# serial_led_controller.net
KiCad netlist of a schematic drawn in EAGLE
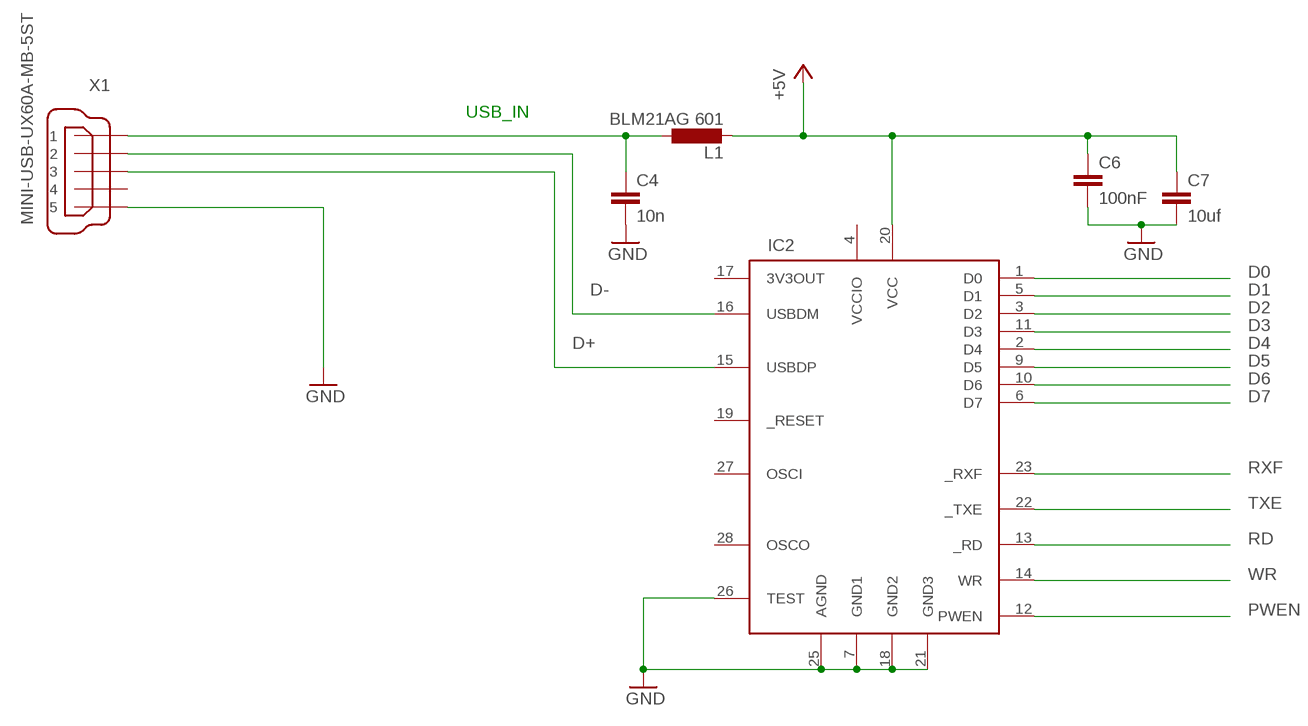
[diagram p0: schematic, sheet 1]
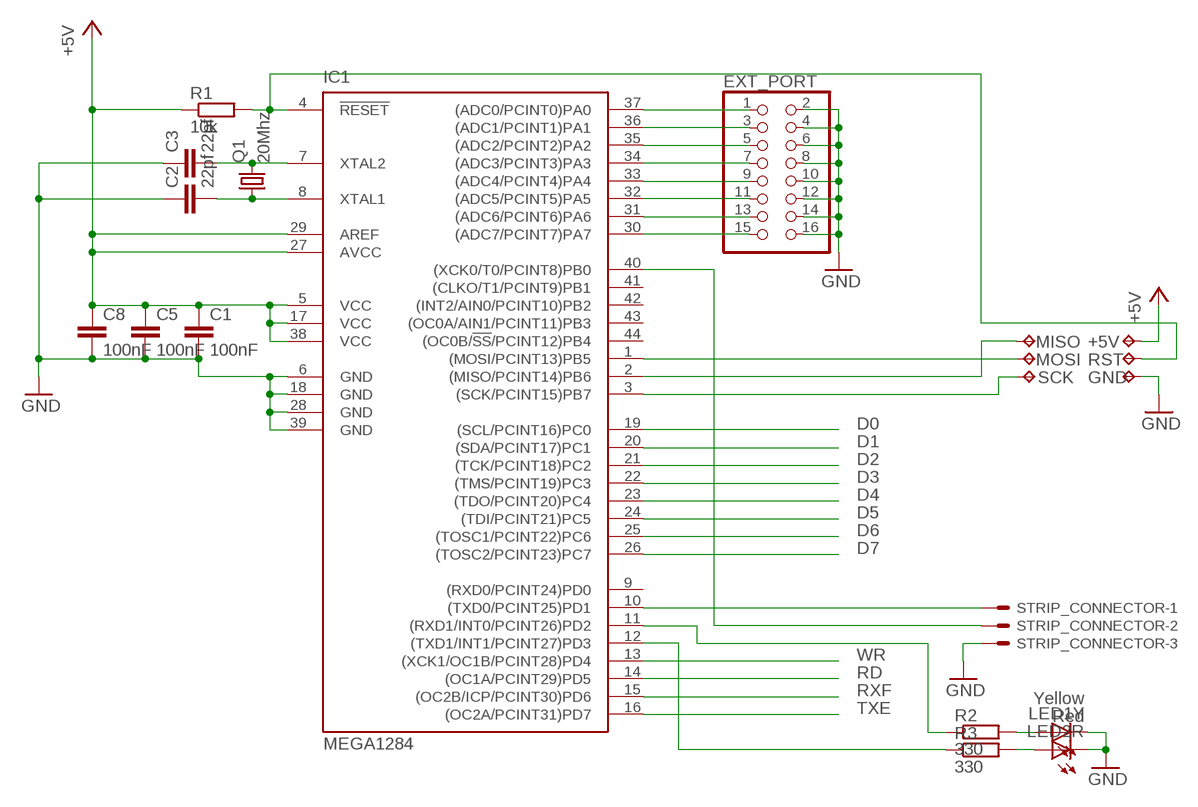
[diagram p1: schematic, sheet 2]

(export (version "E")
  (design (tool "Eeschema 10.0.6"))
  (components
    (comp (ref "+5V")
      (value "TPTP19R")
      (footprint "eagle-import:TP19R")
      (libsource (lib "eagle-import") (part "TPTP19R"))
    )
    (comp (ref "C1")
      (value "100nF")
      (footprint "eagle-import:C0603K")
      (libsource (lib "eagle-import") (part "C-EUC0603K"))
    )
    (comp (ref "C2")
      (value "22pf")
      (footprint "eagle-import:C0603K")
      (libsource (lib "eagle-import") (part "C-EUC0603K"))
    )
    (comp (ref "C3")
      (value "22pf")
      (footprint "eagle-import:C0603K")
      (libsource (lib "eagle-import") (part "C-EUC0603K"))
    )
    (comp (ref "C5")
      (value "100nF")
      (footprint "eagle-import:C0603K")
      (libsource (lib "eagle-import") (part "C-EUC0603K"))
    )
    (comp (ref "C8")
      (value "100nF")
      (footprint "eagle-import:C0603K")
      (libsource (lib "eagle-import") (part "C-EUC0603K"))
    )
    (comp (ref "EXT_PORT")
      (value "PINHD-2X8")
      (footprint "eagle-import:2X08")
      (libsource (lib "eagle-import") (part "PINHD-2X8"))
    )
    (comp (ref "GND")
      (value "TPTP19R")
      (footprint "eagle-import:TP19R")
      (libsource (lib "eagle-import") (part "TPTP19R"))
    )
    (comp (ref "IC1")
      (value "MEGA1284")
      (footprint "eagle-import:TQFP44")
      (libsource (lib "eagle-import") (part "MEGA164P/324P/644P-AU"))
    )
    (comp (ref "LED1Y")
      (value "Yellow")
      (footprint "eagle-import:CHIP-LED0603")
      (libsource (lib "eagle-import") (part "LEDCHIP-LED0603"))
    )
    (comp (ref "LED2R")
      (value "Red")
      (footprint "eagle-import:CHIP-LED0603")
      (libsource (lib "eagle-import") (part "LEDCHIP-LED0603"))
    )
    (comp (ref "MISO")
      (value "TPTP19R")
      (footprint "eagle-import:TP19R")
      (libsource (lib "eagle-import") (part "TPTP19R"))
    )
    (comp (ref "MOSI")
      (value "TPTP19R")
      (footprint "eagle-import:TP19R")
      (libsource (lib "eagle-import") (part "TPTP19R"))
    )
    (comp (ref "Q1")
      (value "20Mhz")
      (footprint "eagle-import:SM49")
      (libsource (lib "eagle-import") (part "CRYSTALSM49"))
    )
    (comp (ref "R1")
      (value "10k")
      (footprint "eagle-import:R0603")
      (libsource (lib "eagle-import") (part "R-EU_603"))
    )
    (comp (ref "R2")
      (value "330")
      (footprint "eagle-import:R0603")
      (libsource (lib "eagle-import") (part "R-EU_603"))
    )
    (comp (ref "R3")
      (value "330")
      (footprint "eagle-import:R0603")
      (libsource (lib "eagle-import") (part "R-EU_603"))
    )
    (comp (ref "RST")
      (value "TPTP19R")
      (footprint "eagle-import:TP19R")
      (libsource (lib "eagle-import") (part "TPTP19R"))
    )
    (comp (ref "SCK")
      (value "TPTP19R")
      (footprint "eagle-import:TP19R")
      (libsource (lib "eagle-import") (part "TPTP19R"))
    )
    (comp (ref "STRIP_CONNECTOR")
      (value "22-27-2031-03")
      (footprint "eagle-import:6410-03")
      (libsource (lib "eagle-import") (part "22-?-0327-2031"))
    )
    (comp (ref "C4")
      (value "10n")
      (footprint "eagle-import:C0603K")
      (libsource (lib "eagle-import") (part "C-EUC0603K"))
    )
    (comp (ref "C6")
      (value "100nF")
      (footprint "eagle-import:C0603K")
      (libsource (lib "eagle-import") (part "C-EUC0603K"))
    )
    (comp (ref "C7")
      (value "10uf")
      (footprint "eagle-import:C0603K")
      (libsource (lib "eagle-import") (part "C-EUC0603K"))
    )
    (comp (ref "IC2")
      (value "FT245RL")
      (footprint "eagle-import:SSOP28DB")
      (libsource (lib "eagle-import") (part "FT245RL"))
    )
    (comp (ref "L1")
      (value "BLM21AG 601")
      (footprint "eagle-import:L805")
      (libsource (lib "eagle-import") (part "L-EUL805"))
    )
    (comp (ref "X1")
      (value "MINI-USB-UX60A-MB-5ST")
      (footprint "eagle-import:UX60A-MB-5ST")
      (libsource (lib "eagle-import") (part "MINI-USB-UX60A-MB-5ST"))
    )
  )
  (nets
    (net (code "1") (name "+5V") (class "Default")
      (node (ref "+5V") (pin "TP") (pinfunction "TP_TP") (pintype "input"))
      (node (ref "C1") (pin "1") (pinfunction "1_1") (pintype "passive"))
      (node (ref "C5") (pin "1") (pinfunction "1_1") (pintype "passive"))
      (node (ref "C6") (pin "1") (pinfunction "1_1") (pintype "passive"))
      (node (ref "C7") (pin "1") (pinfunction "1_1") (pintype "passive"))
      (node (ref "C8") (pin "1") (pinfunction "1_1") (pintype "passive"))
      (node (ref "IC1") (pin "17") (pinfunction "VCC_17") (pintype "power_in"))
      (node (ref "IC1") (pin "27") (pinfunction "AVCC_27") (pintype "power_in"))
      (node (ref "IC1") (pin "29") (pinfunction "AREF_29") (pintype "power_in"))
      (node (ref "IC1") (pin "38") (pinfunction "VCC_38") (pintype "power_in"))
      (node (ref "IC1") (pin "5") (pinfunction "VCC_5") (pintype "power_in"))
      (node (ref "IC2") (pin "20") (pinfunction "VCC_20") (pintype "power_in"))
      (node (ref "L1") (pin "2") (pinfunction "2_2") (pintype "passive"))
      (node (ref "R1") (pin "1") (pinfunction "1_1") (pintype "passive"))
    )
    (net (code "2") (name "D+") (class "Default")
      (node (ref "IC2") (pin "15") (pinfunction "USBDP_15") (pintype "bidirectional"))
      (node (ref "X1") (pin "3") (pinfunction "3_3") (pintype "input"))
    )
    (net (code "3") (name "D-") (class "Default")
      (node (ref "IC2") (pin "16") (pinfunction "USBDM_16") (pintype "bidirectional"))
      (node (ref "X1") (pin "2") (pinfunction "2_2") (pintype "input"))
    )
    (net (code "4") (name "D0") (class "Default")
      (node (ref "IC1") (pin "19") (pinfunction "(SCL/PCINT16)PC0_19") (pintype "bidirectional"))
      (node (ref "IC2") (pin "1") (pinfunction "D0_1") (pintype "output"))
    )
    (net (code "5") (name "D1") (class "Default")
      (node (ref "IC1") (pin "20") (pinfunction "(SDA/PCINT17)PC1_20") (pintype "bidirectional"))
      (node (ref "IC2") (pin "5") (pinfunction "D1_5") (pintype "input"))
    )
    (net (code "6") (name "D2") (class "Default")
      (node (ref "IC1") (pin "21") (pinfunction "(TCK/PCINT18)PC2_21") (pintype "bidirectional"))
      (node (ref "IC2") (pin "3") (pinfunction "D2_3") (pintype "output"))
    )
    (net (code "7") (name "D3") (class "Default")
      (node (ref "IC1") (pin "22") (pinfunction "(TMS/PCINT19)PC3_22") (pintype "bidirectional"))
      (node (ref "IC2") (pin "11") (pinfunction "D3_11") (pintype "input"))
    )
    (net (code "8") (name "D4") (class "Default")
      (node (ref "IC1") (pin "23") (pinfunction "(TDO/PCINT20)PC4_23") (pintype "bidirectional"))
      (node (ref "IC2") (pin "2") (pinfunction "D4_2") (pintype "output"))
    )
    (net (code "9") (name "D5") (class "Default")
      (node (ref "IC1") (pin "24") (pinfunction "(TDI/PCINT21)PC5_24") (pintype "bidirectional"))
      (node (ref "IC2") (pin "9") (pinfunction "D5_9") (pintype "input"))
    )
    (net (code "10") (name "D6") (class "Default")
      (node (ref "IC1") (pin "25") (pinfunction "(TOSC1/PCINT22)PC6_25") (pintype "bidirectional"))
      (node (ref "IC2") (pin "10") (pinfunction "D6_10") (pintype "input"))
    )
    (net (code "11") (name "D7") (class "Default")
      (node (ref "IC1") (pin "26") (pinfunction "(TOSC2/PCINT23)PC7_26") (pintype "bidirectional"))
      (node (ref "IC2") (pin "6") (pinfunction "D7_6") (pintype "input"))
    )
    (net (code "12") (name "GND") (class "Default")
      (node (ref "C1") (pin "2") (pinfunction "2_2") (pintype "passive"))
      (node (ref "C2") (pin "1") (pinfunction "1_1") (pintype "passive"))
      (node (ref "C3") (pin "1") (pinfunction "1_1") (pintype "passive"))
      (node (ref "C4") (pin "2") (pinfunction "2_2") (pintype "passive"))
      (node (ref "C5") (pin "2") (pinfunction "2_2") (pintype "passive"))
      (node (ref "C6") (pin "2") (pinfunction "2_2") (pintype "passive"))
      (node (ref "C7") (pin "2") (pinfunction "2_2") (pintype "passive"))
      (node (ref "C8") (pin "2") (pinfunction "2_2") (pintype "passive"))
      (node (ref "EXT_PORT") (pin "10") (pinfunction "10_10") (pintype "passive"))
      (node (ref "EXT_PORT") (pin "12") (pinfunction "12_12") (pintype "passive"))
      (node (ref "EXT_PORT") (pin "14") (pinfunction "14_14") (pintype "passive"))
      (node (ref "EXT_PORT") (pin "16") (pinfunction "16_16") (pintype "passive"))
      (node (ref "EXT_PORT") (pin "2") (pinfunction "2_2") (pintype "passive"))
      (node (ref "EXT_PORT") (pin "4") (pinfunction "4_4") (pintype "passive"))
      (node (ref "EXT_PORT") (pin "6") (pinfunction "6_6") (pintype "passive"))
      (node (ref "EXT_PORT") (pin "8") (pinfunction "8_8") (pintype "passive"))
      (node (ref "GND") (pin "TP") (pinfunction "TP_TP") (pintype "input"))
      (node (ref "IC1") (pin "18") (pinfunction "GND_18") (pintype "power_in"))
      (node (ref "IC1") (pin "28") (pinfunction "GND_28") (pintype "power_in"))
      (node (ref "IC1") (pin "39") (pinfunction "GND_39") (pintype "power_in"))
      (node (ref "IC1") (pin "6") (pinfunction "GND_6") (pintype "power_in"))
      (node (ref "IC2") (pin "18") (pinfunction "GND2_18") (pintype "power_in"))
      (node (ref "IC2") (pin "21") (pinfunction "GND3_21") (pintype "power_in"))
      (node (ref "IC2") (pin "25") (pinfunction "AGND_25") (pintype "power_in"))
      (node (ref "IC2") (pin "26") (pinfunction "TEST_26") (pintype "input"))
      (node (ref "IC2") (pin "7") (pinfunction "GND1_7") (pintype "power_in"))
      (node (ref "LED1Y") (pin "C") (pinfunction "C_C") (pintype "passive"))
      (node (ref "LED2R") (pin "C") (pinfunction "C_C") (pintype "passive"))
      (node (ref "STRIP_CONNECTOR") (pin "3") (pinfunction "S_3") (pintype "passive"))
      (node (ref "X1") (pin "5") (pinfunction "5_5") (pintype "input"))
    )
    (net (code "13") (name "Net-(C4-Pad1)") (class "Default")
      (node (ref "C4") (pin "1") (pinfunction "1_1") (pintype "passive"))
      (node (ref "L1") (pin "1") (pinfunction "1_1") (pintype "passive"))
      (node (ref "X1") (pin "1") (pinfunction "1_1") (pintype "input"))
    )
    (net (code "14") (name "Net-(IC1-(ADC0{slash}PCINT0)PA0)") (class "Default")
      (node (ref "EXT_PORT") (pin "1") (pinfunction "1_1") (pintype "passive"))
      (node (ref "IC1") (pin "37") (pinfunction "(ADC0/PCINT0)PA0_37") (pintype "bidirectional"))
    )
    (net (code "15") (name "Net-(IC1-(ADC1{slash}PCINT1)PA1)") (class "Default")
      (node (ref "EXT_PORT") (pin "3") (pinfunction "3_3") (pintype "passive"))
      (node (ref "IC1") (pin "36") (pinfunction "(ADC1/PCINT1)PA1_36") (pintype "bidirectional"))
    )
    (net (code "16") (name "Net-(IC1-(ADC2{slash}PCINT2)PA2)") (class "Default")
      (node (ref "EXT_PORT") (pin "5") (pinfunction "5_5") (pintype "passive"))
      (node (ref "IC1") (pin "35") (pinfunction "(ADC2/PCINT2)PA2_35") (pintype "bidirectional"))
    )
    (net (code "17") (name "Net-(IC1-(ADC3{slash}PCINT3)PA3)") (class "Default")
      (node (ref "EXT_PORT") (pin "7") (pinfunction "7_7") (pintype "passive"))
      (node (ref "IC1") (pin "34") (pinfunction "(ADC3/PCINT3)PA3_34") (pintype "bidirectional"))
    )
    (net (code "18") (name "Net-(IC1-(ADC4{slash}PCINT4)PA4)") (class "Default")
      (node (ref "EXT_PORT") (pin "9") (pinfunction "9_9") (pintype "passive"))
      (node (ref "IC1") (pin "33") (pinfunction "(ADC4/PCINT4)PA4_33") (pintype "bidirectional"))
    )
    (net (code "19") (name "Net-(IC1-(ADC5{slash}PCINT5)PA5)") (class "Default")
      (node (ref "EXT_PORT") (pin "11") (pinfunction "11_11") (pintype "passive"))
      (node (ref "IC1") (pin "32") (pinfunction "(ADC5/PCINT5)PA5_32") (pintype "bidirectional"))
    )
    (net (code "20") (name "Net-(IC1-(ADC6{slash}PCINT6)PA6)") (class "Default")
      (node (ref "EXT_PORT") (pin "13") (pinfunction "13_13") (pintype "passive"))
      (node (ref "IC1") (pin "31") (pinfunction "(ADC6/PCINT6)PA6_31") (pintype "bidirectional"))
    )
    (net (code "21") (name "Net-(IC1-(ADC7{slash}PCINT7)PA7)") (class "Default")
      (node (ref "EXT_PORT") (pin "15") (pinfunction "15_15") (pintype "passive"))
      (node (ref "IC1") (pin "30") (pinfunction "(ADC7/PCINT7)PA7_30") (pintype "bidirectional"))
    )
    (net (code "22") (name "Net-(IC1-(MISO{slash}PCINT14)PB6)") (class "Default")
      (node (ref "IC1") (pin "2") (pinfunction "(MISO/PCINT14)PB6_2") (pintype "bidirectional"))
      (node (ref "MISO") (pin "TP") (pinfunction "TP_TP") (pintype "input"))
    )
    (net (code "23") (name "Net-(IC1-(MOSI{slash}PCINT13)PB5)") (class "Default")
      (node (ref "IC1") (pin "1") (pinfunction "(MOSI/PCINT13)PB5_1") (pintype "bidirectional"))
      (node (ref "MOSI") (pin "TP") (pinfunction "TP_TP") (pintype "input"))
    )
    (net (code "24") (name "Net-(IC1-(RXD1{slash}INT0{slash}PCINT26)PD2)") (class "Default")
      (node (ref "IC1") (pin "11") (pinfunction "(RXD1/INT0/PCINT26)PD2_11") (pintype "bidirectional"))
      (node (ref "R2") (pin "1") (pinfunction "1_1") (pintype "passive"))
    )
    (net (code "25") (name "Net-(IC1-(SCK{slash}PCINT15)PB7)") (class "Default")
      (node (ref "IC1") (pin "3") (pinfunction "(SCK/PCINT15)PB7_3") (pintype "bidirectional"))
      (node (ref "SCK") (pin "TP") (pinfunction "TP_TP") (pintype "input"))
    )
    (net (code "26") (name "Net-(IC1-(TXD0{slash}PCINT25)PD1)") (class "Default")
      (node (ref "IC1") (pin "10") (pinfunction "(TXD0/PCINT25)PD1_10") (pintype "bidirectional"))
      (node (ref "STRIP_CONNECTOR") (pin "1") (pinfunction "S_1") (pintype "passive"))
    )
    (net (code "27") (name "Net-(IC1-(TXD1{slash}INT1{slash}PCINT27)PD3)") (class "Default")
      (node (ref "IC1") (pin "12") (pinfunction "(TXD1/INT1/PCINT27)PD3_12") (pintype "bidirectional"))
      (node (ref "R3") (pin "1") (pinfunction "1_1") (pintype "passive"))
    )
    (net (code "28") (name "Net-(IC1-(XCK0{slash}T0{slash}PCINT8)PB0)") (class "Default")
      (node (ref "IC1") (pin "40") (pinfunction "(XCK0/T0/PCINT8)PB0_40") (pintype "bidirectional"))
      (node (ref "STRIP_CONNECTOR") (pin "2") (pinfunction "S_2") (pintype "passive"))
    )
    (net (code "29") (name "Net-(IC1-XTAL1)") (class "Default")
      (node (ref "C2") (pin "2") (pinfunction "2_2") (pintype "passive"))
      (node (ref "IC1") (pin "8") (pinfunction "XTAL1_8") (pintype "input"))
      (node (ref "Q1") (pin "1") (pinfunction "1_1") (pintype "passive"))
    )
    (net (code "30") (name "Net-(IC1-XTAL2)") (class "Default")
      (node (ref "C3") (pin "2") (pinfunction "2_2") (pintype "passive"))
      (node (ref "IC1") (pin "7") (pinfunction "XTAL2_7") (pintype "output"))
      (node (ref "Q1") (pin "2") (pinfunction "2_2") (pintype "passive"))
    )
    (net (code "31") (name "Net-(IC1-~{RESET})") (class "Default")
      (node (ref "IC1") (pin "4") (pinfunction "~{RESET}_4") (pintype "input"))
      (node (ref "R1") (pin "2") (pinfunction "2_2") (pintype "passive"))
      (node (ref "RST") (pin "TP") (pinfunction "TP_TP") (pintype "input"))
    )
    (net (code "32") (name "Net-(LED1Y-PadA)") (class "Default")
      (node (ref "LED1Y") (pin "A") (pinfunction "A_A") (pintype "passive"))
      (node (ref "R2") (pin "2") (pinfunction "2_2") (pintype "passive"))
    )
    (net (code "33") (name "Net-(LED2R-PadA)") (class "Default")
      (node (ref "LED2R") (pin "A") (pinfunction "A_A") (pintype "passive"))
      (node (ref "R3") (pin "2") (pinfunction "2_2") (pintype "passive"))
    )
    (net (code "34") (name "PWEN") (class "Default")
      (node (ref "IC2") (pin "12") (pinfunction "PWEN_12") (pintype "bidirectional"))
    )
    (net (code "35") (name "RD") (class "Default")
      (node (ref "IC1") (pin "14") (pinfunction "(OC1A/PCINT29)PD5_14") (pintype "bidirectional"))
      (node (ref "IC2") (pin "13") (pinfunction "_RD_13") (pintype "bidirectional"))
    )
    (net (code "36") (name "RXF") (class "Default")
      (node (ref "IC1") (pin "15") (pinfunction "(OC2B/ICP/PCINT30)PD6_15") (pintype "bidirectional"))
      (node (ref "IC2") (pin "23") (pinfunction "_RXF_23") (pintype "bidirectional"))
    )
    (net (code "37") (name "TXE") (class "Default")
      (node (ref "IC1") (pin "16") (pinfunction "(OC2A/PCINT31)PD7_16") (pintype "bidirectional"))
      (node (ref "IC2") (pin "22") (pinfunction "_TXE_22") (pintype "bidirectional"))
    )
    (net (code "38") (name "VCCIO") (class "Default")
      (node (ref "IC2") (pin "4") (pinfunction "VCCIO_4") (pintype "power_in"))
    )
    (net (code "39") (name "WR") (class "Default")
      (node (ref "IC1") (pin "13") (pinfunction "(XCK1/OC1B/PCINT28)PD4_13") (pintype "bidirectional"))
      (node (ref "IC2") (pin "14") (pinfunction "WR_14") (pintype "bidirectional"))
    )
    (net (code "40") (name "unconnected-(IC1-(CLKO{slash}T1{slash}PCINT9)PB1-Pad41)") (class "Default")
      (node (ref "IC1") (pin "41") (pinfunction "(CLKO/T1/PCINT9)PB1_41") (pintype "bidirectional"))
    )
    (net (code "41") (name "unconnected-(IC1-(INT2{slash}AIN0{slash}PCINT10)PB2-Pad42)") (class "Default")
      (node (ref "IC1") (pin "42") (pinfunction "(INT2/AIN0/PCINT10)PB2_42") (pintype "bidirectional"))
    )
    (net (code "42") (name "unconnected-(IC1-(OC0A{slash}AIN1{slash}PCINT11)PB3-Pad43)") (class "Default")
      (node (ref "IC1") (pin "43") (pinfunction "(OC0A/AIN1/PCINT11)PB3_43") (pintype "bidirectional"))
    )
    (net (code "43") (name "unconnected-(IC1-(OC0B{slash}~{SS}{slash}PCINT12)PB4-Pad44)") (class "Default")
      (node (ref "IC1") (pin "44") (pinfunction "(OC0B/~{SS}/PCINT12)PB4_44") (pintype "bidirectional"))
    )
    (net (code "44") (name "unconnected-(IC1-(RXD0{slash}PCINT24)PD0-Pad9)") (class "Default")
      (node (ref "IC1") (pin "9") (pinfunction "(RXD0/PCINT24)PD0_9") (pintype "bidirectional"))
    )
    (net (code "45") (name "unconnected-(IC2-3V3OUT-Pad17)") (class "Default")
      (node (ref "IC2") (pin "17") (pinfunction "3V3OUT_17") (pintype "output"))
    )
    (net (code "46") (name "unconnected-(IC2-OSCI-Pad27)") (class "Default")
      (node (ref "IC2") (pin "27") (pinfunction "OSCI_27") (pintype "input"))
    )
    (net (code "47") (name "unconnected-(IC2-OSCO-Pad28)") (class "Default")
      (node (ref "IC2") (pin "28") (pinfunction "OSCO_28") (pintype "output"))
    )
    (net (code "48") (name "unconnected-(IC2-_RESET-Pad19)") (class "Default")
      (node (ref "IC2") (pin "19") (pinfunction "_RESET_19") (pintype "input"))
    )
    (net (code "49") (name "unconnected-(X1-Pad4)") (class "Default")
      (node (ref "X1") (pin "4") (pinfunction "4_4") (pintype "input"))
    )
  )
)
